# Upper.net
KiCad netlist of a schematic drawn in Altium Designer
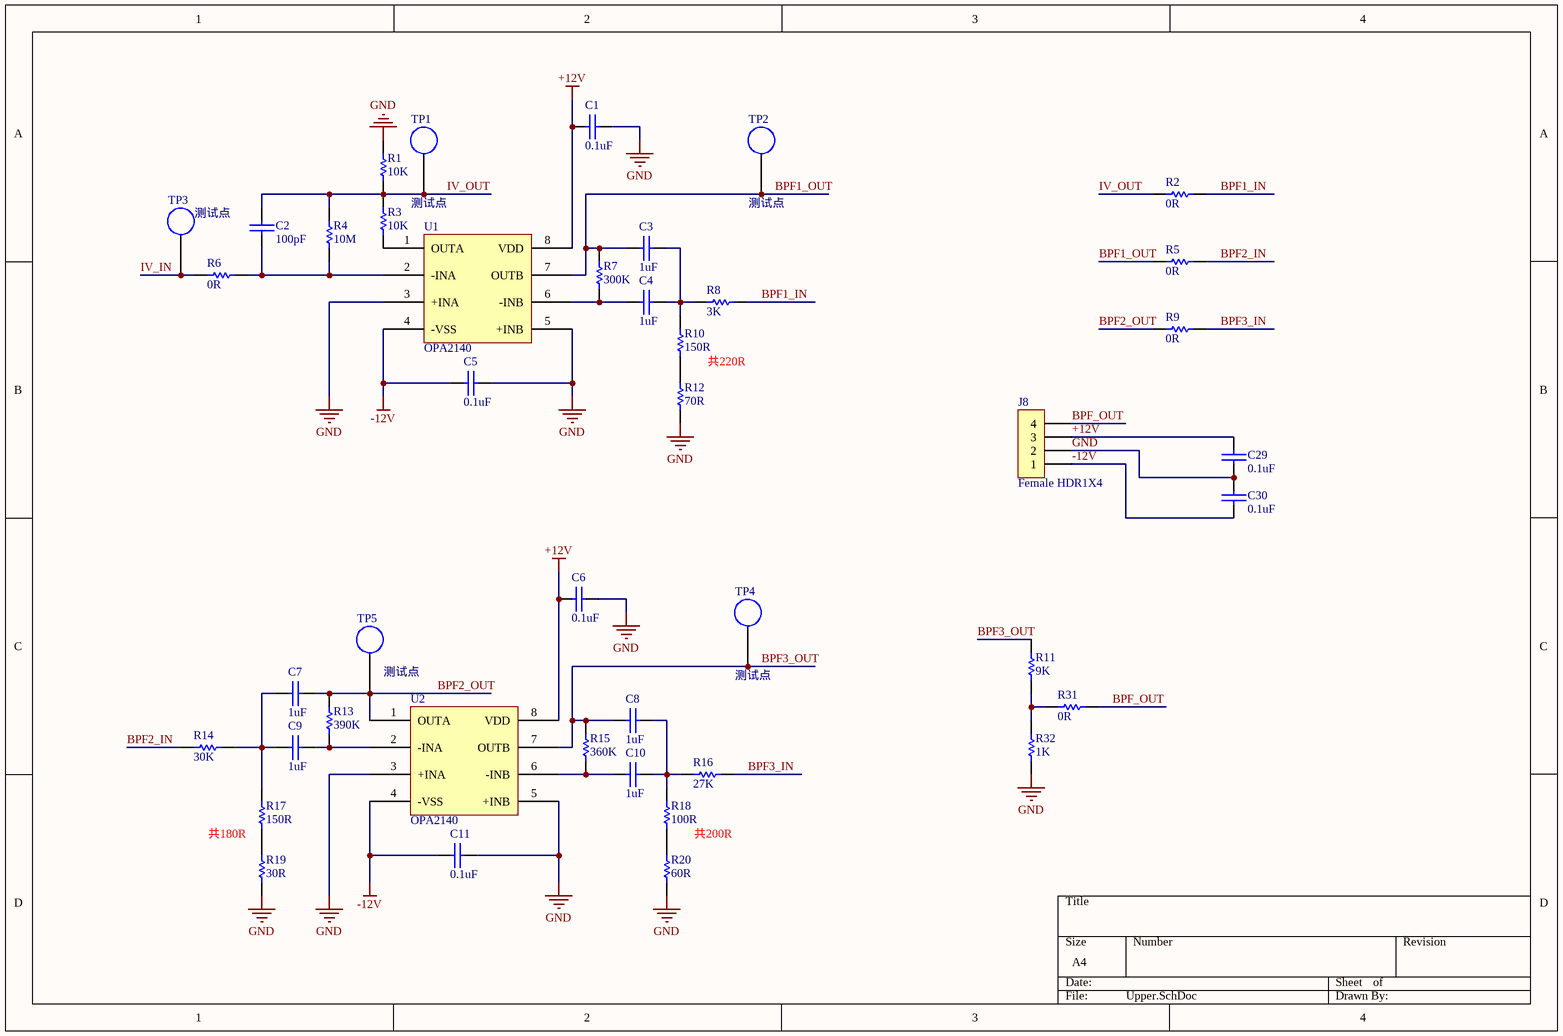
[diagram p0: Upper.SchDoc]

(export (version "E")
  (design (tool "Eeschema 10.0.6"))
  (components
    (comp (ref "C1")
      (value "0.1uF")
      (footprint "0603C")
      (description "无极性电容")
      (libsource (lib "电容") (part "CAP"))
    )
    (comp (ref "C2")
      (value "100pF")
      (footprint "0603C")
      (description "无极性电容")
      (libsource (lib "电容") (part "CAP"))
    )
    (comp (ref "C3")
      (value "1uF")
      (footprint "0603C")
      (description "无极性电容")
      (libsource (lib "电容") (part "CAP"))
    )
    (comp (ref "C4")
      (value "1uF")
      (footprint "0603C")
      (description "无极性电容")
      (libsource (lib "电容") (part "CAP"))
    )
    (comp (ref "C5")
      (value "0.1uF")
      (footprint "0603C")
      (description "无极性电容")
      (libsource (lib "电容") (part "CAP"))
    )
    (comp (ref "C6")
      (value "0.1uF")
      (footprint "0603C")
      (description "无极性电容")
      (libsource (lib "电容") (part "CAP"))
    )
    (comp (ref "C7")
      (value "1uF")
      (footprint "1206C")
      (description "无极性电容")
      (libsource (lib "电容") (part "CAP"))
    )
    (comp (ref "C8")
      (value "1uF")
      (footprint "0603C")
      (description "无极性电容")
      (libsource (lib "电容") (part "CAP"))
    )
    (comp (ref "C9")
      (value "1uF")
      (footprint "1206C")
      (description "无极性电容")
      (libsource (lib "电容") (part "CAP"))
    )
    (comp (ref "C10")
      (value "1uF")
      (footprint "0603C")
      (description "无极性电容")
      (libsource (lib "电容") (part "CAP"))
    )
    (comp (ref "C11")
      (value "0.1uF")
      (footprint "0603C")
      (description "无极性电容")
      (libsource (lib "电容") (part "CAP"))
    )
    (comp (ref "C29")
      (value "0.1uF")
      (footprint "0603C")
      (description "无极性电容")
      (libsource (lib "电容") (part "CAP"))
    )
    (comp (ref "C30")
      (value "0.1uF")
      (footprint "0603C")
      (description "无极性电容")
      (libsource (lib "电容") (part "CAP"))
    )
    (comp (ref "J8")
      (value "Female HDR1X4")
      (footprint "Fe-HDR1X4/2.54-S")
      (libsource (lib "排母") (part "Female HDR1X4"))
    )
    (comp (ref "R1") (value "10K") (footprint "0603R") (libsource (lib "电阻") (part "RES")))
    (comp (ref "R2") (value "0R") (footprint "0603R") (libsource (lib "电阻") (part "RES")))
    (comp (ref "R3") (value "10K") (footprint "0603R") (libsource (lib "电阻") (part "RES")))
    (comp (ref "R4") (value "10M") (footprint "0603R") (libsource (lib "电阻") (part "RES")))
    (comp (ref "R5") (value "0R") (footprint "0603R") (libsource (lib "电阻") (part "RES")))
    (comp (ref "R6") (value "0R") (footprint "0603R") (libsource (lib "电阻") (part "RES")))
    (comp (ref "R7") (value "300K") (footprint "0603R") (libsource (lib "电阻") (part "RES")))
    (comp (ref "R8") (value "3K") (footprint "0603R") (libsource (lib "电阻") (part "RES")))
    (comp (ref "R9") (value "0R") (footprint "0603R") (libsource (lib "电阻") (part "RES")))
    (comp (ref "R10") (value "150R") (footprint "0603R") (libsource (lib "电阻") (part "RES")))
    (comp (ref "R11") (value "9K") (footprint "0603R") (libsource (lib "电阻") (part "RES")))
    (comp (ref "R12") (value "70R") (footprint "0603R") (libsource (lib "电阻") (part "RES")))
    (comp (ref "R13") (value "390K") (footprint "0603R") (libsource (lib "电阻") (part "RES")))
    (comp (ref "R14") (value "30K") (footprint "0603R") (libsource (lib "电阻") (part "RES")))
    (comp (ref "R15") (value "360K") (footprint "0603R") (libsource (lib "电阻") (part "RES")))
    (comp (ref "R16") (value "27K") (footprint "0603R") (libsource (lib "电阻") (part "RES")))
    (comp (ref "R17") (value "150R") (footprint "0603R") (libsource (lib "电阻") (part "RES")))
    (comp (ref "R18") (value "100R") (footprint "0603R") (libsource (lib "电阻") (part "RES")))
    (comp (ref "R19") (value "30R") (footprint "0603R") (libsource (lib "电阻") (part "RES")))
    (comp (ref "R20") (value "60R") (footprint "0603R") (libsource (lib "电阻") (part "RES")))
    (comp (ref "R31") (value "0R") (footprint "0603R") (libsource (lib "电阻") (part "RES")))
    (comp (ref "R32") (value "1K") (footprint "0603R") (libsource (lib "电阻") (part "RES")))
    (comp (ref "TP1") (value "测试点") (footprint "TP") (libsource (lib "固定柱和测试点") (part "测试点")))
    (comp (ref "TP2") (value "测试点") (footprint "TP") (libsource (lib "固定柱和测试点") (part "测试点")))
    (comp (ref "TP3") (value "测试点") (footprint "TP") (libsource (lib "固定柱和测试点") (part "测试点")))
    (comp (ref "TP4") (value "测试点") (footprint "TP") (libsource (lib "固定柱和测试点") (part "测试点")))
    (comp (ref "TP5") (value "测试点") (footprint "TP") (libsource (lib "固定柱和测试点") (part "测试点")))
    (comp (ref "U1") (value "OPA2140") (footprint "SOP8") (libsource (lib "未分类IC") (part "NE5532")))
    (comp (ref "U2") (value "OPA2140") (footprint "SOP8") (libsource (lib "未分类IC") (part "NE5532")))
  )
  (nets
    (net (code "1") (name "+12V") (class "Default")
      (node (ref "C1") (pin "1") (pinfunction "1_1") (pintype "passive"))
      (node (ref "C29") (pin "2") (pinfunction "2_2") (pintype "passive"))
      (node (ref "C6") (pin "1") (pinfunction "1_1") (pintype "passive"))
      (node (ref "J8") (pin "3") (pinfunction "3_3") (pintype "passive"))
      (node (ref "U1") (pin "8") (pinfunction "VDD_8") (pintype "passive"))
      (node (ref "U2") (pin "8") (pinfunction "VDD_8") (pintype "passive"))
    )
    (net (code "2") (name "-12V") (class "Default")
      (node (ref "C11") (pin "1") (pinfunction "1_1") (pintype "passive"))
      (node (ref "C30") (pin "1") (pinfunction "1_1") (pintype "passive"))
      (node (ref "C5") (pin "1") (pinfunction "1_1") (pintype "passive"))
      (node (ref "J8") (pin "1") (pinfunction "1_1") (pintype "passive"))
      (node (ref "U1") (pin "4") (pinfunction "-VSS_4") (pintype "passive"))
      (node (ref "U2") (pin "4") (pinfunction "-VSS_4") (pintype "passive"))
    )
    (net (code "3") (name "/BPF1_IN") (class "Default")
      (node (ref "R2") (pin "2") (pinfunction "2_2") (pintype "passive"))
      (node (ref "R8") (pin "1") (pinfunction "1_1") (pintype "passive"))
    )
    (net (code "4") (name "/BPF1_OUT") (class "Default")
      (node (ref "C3") (pin "2") (pinfunction "2_2") (pintype "passive"))
      (node (ref "R5") (pin "1") (pinfunction "1_1") (pintype "passive"))
      (node (ref "R7") (pin "2") (pinfunction "2_2") (pintype "passive"))
      (node (ref "TP2") (pin "1") (pinfunction "TP_1") (pintype "passive"))
      (node (ref "U1") (pin "7") (pinfunction "OUTB_7") (pintype "passive"))
    )
    (net (code "5") (name "/BPF2_IN") (class "Default")
      (node (ref "R14") (pin "2") (pinfunction "2_2") (pintype "passive"))
      (node (ref "R5") (pin "2") (pinfunction "2_2") (pintype "passive"))
    )
    (net (code "6") (name "/BPF2_OUT") (class "Default")
      (node (ref "C7") (pin "1") (pinfunction "1_1") (pintype "passive"))
      (node (ref "R13") (pin "2") (pinfunction "2_2") (pintype "passive"))
      (node (ref "R9") (pin "1") (pinfunction "1_1") (pintype "passive"))
      (node (ref "TP5") (pin "1") (pinfunction "TP_1") (pintype "passive"))
      (node (ref "U2") (pin "1") (pinfunction "OUTA_1") (pintype "passive"))
    )
    (net (code "7") (name "/BPF3_IN") (class "Default")
      (node (ref "R16") (pin "1") (pinfunction "1_1") (pintype "passive"))
      (node (ref "R9") (pin "2") (pinfunction "2_2") (pintype "passive"))
    )
    (net (code "8") (name "/BPF3_OUT") (class "Default")
      (node (ref "C8") (pin "2") (pinfunction "2_2") (pintype "passive"))
      (node (ref "R11") (pin "2") (pinfunction "2_2") (pintype "passive"))
      (node (ref "R15") (pin "2") (pinfunction "2_2") (pintype "passive"))
      (node (ref "TP4") (pin "1") (pinfunction "TP_1") (pintype "passive"))
      (node (ref "U2") (pin "7") (pinfunction "OUTB_7") (pintype "passive"))
    )
    (net (code "9") (name "/BPF_OUT") (class "Default")
      (node (ref "J8") (pin "4") (pinfunction "4_4") (pintype "passive"))
      (node (ref "R31") (pin "1") (pinfunction "1_1") (pintype "passive"))
    )
    (net (code "10") (name "/IV_IN") (class "Default")
      (node (ref "R6") (pin "2") (pinfunction "2_2") (pintype "passive"))
      (node (ref "TP3") (pin "1") (pinfunction "TP_1") (pintype "passive"))
    )
    (net (code "11") (name "/IV_OUT") (class "Default")
      (node (ref "C2") (pin "1") (pinfunction "1_1") (pintype "passive"))
      (node (ref "R1") (pin "1") (pinfunction "1_1") (pintype "passive"))
      (node (ref "R2") (pin "1") (pinfunction "1_1") (pintype "passive"))
      (node (ref "R3") (pin "2") (pinfunction "2_2") (pintype "passive"))
      (node (ref "R4") (pin "2") (pinfunction "2_2") (pintype "passive"))
      (node (ref "TP1") (pin "1") (pinfunction "TP_1") (pintype "passive"))
    )
    (net (code "12") (name "GND") (class "Default")
      (node (ref "C1") (pin "2") (pinfunction "2_2") (pintype "passive"))
      (node (ref "C11") (pin "2") (pinfunction "2_2") (pintype "passive"))
      (node (ref "C29") (pin "1") (pinfunction "1_1") (pintype "passive"))
      (node (ref "C30") (pin "2") (pinfunction "2_2") (pintype "passive"))
      (node (ref "C5") (pin "2") (pinfunction "2_2") (pintype "passive"))
      (node (ref "C6") (pin "2") (pinfunction "2_2") (pintype "passive"))
      (node (ref "J8") (pin "2") (pinfunction "2_2") (pintype "passive"))
      (node (ref "R1") (pin "2") (pinfunction "2_2") (pintype "passive"))
      (node (ref "R12") (pin "2") (pinfunction "2_2") (pintype "passive"))
      (node (ref "R19") (pin "2") (pinfunction "2_2") (pintype "passive"))
      (node (ref "R20") (pin "2") (pinfunction "2_2") (pintype "passive"))
      (node (ref "R32") (pin "1") (pinfunction "1_1") (pintype "passive"))
      (node (ref "U1") (pin "3") (pinfunction "+INA_3") (pintype "passive"))
      (node (ref "U1") (pin "5") (pinfunction "+INB_5") (pintype "passive"))
      (node (ref "U2") (pin "3") (pinfunction "+INA_3") (pintype "passive"))
      (node (ref "U2") (pin "5") (pinfunction "+INB_5") (pintype "passive"))
    )
    (net (code "13") (name "Net-(C3-Pad1)") (class "Default")
      (node (ref "C3") (pin "1") (pinfunction "1_1") (pintype "passive"))
      (node (ref "C4") (pin "2") (pinfunction "2_2") (pintype "passive"))
      (node (ref "R10") (pin "1") (pinfunction "1_1") (pintype "passive"))
      (node (ref "R8") (pin "2") (pinfunction "2_2") (pintype "passive"))
    )
    (net (code "14") (name "Net-(C7-Pad2)") (class "Default")
      (node (ref "C7") (pin "2") (pinfunction "2_2") (pintype "passive"))
      (node (ref "C9") (pin "1") (pinfunction "1_1") (pintype "passive"))
      (node (ref "R14") (pin "1") (pinfunction "1_1") (pintype "passive"))
      (node (ref "R17") (pin "1") (pinfunction "1_1") (pintype "passive"))
    )
    (net (code "15") (name "Net-(C10-Pad2)") (class "Default")
      (node (ref "C10") (pin "2") (pinfunction "2_2") (pintype "passive"))
      (node (ref "C8") (pin "1") (pinfunction "1_1") (pintype "passive"))
      (node (ref "R16") (pin "2") (pinfunction "2_2") (pintype "passive"))
      (node (ref "R18") (pin "1") (pinfunction "1_1") (pintype "passive"))
    )
    (net (code "16") (name "Net-(R10-Pad2)") (class "Default")
      (node (ref "R10") (pin "2") (pinfunction "2_2") (pintype "passive"))
      (node (ref "R12") (pin "1") (pinfunction "1_1") (pintype "passive"))
    )
    (net (code "17") (name "Net-(R11-Pad1)") (class "Default")
      (node (ref "R11") (pin "1") (pinfunction "1_1") (pintype "passive"))
      (node (ref "R31") (pin "2") (pinfunction "2_2") (pintype "passive"))
      (node (ref "R32") (pin "2") (pinfunction "2_2") (pintype "passive"))
    )
    (net (code "18") (name "Net-(R17-Pad2)") (class "Default")
      (node (ref "R17") (pin "2") (pinfunction "2_2") (pintype "passive"))
      (node (ref "R19") (pin "1") (pinfunction "1_1") (pintype "passive"))
    )
    (net (code "19") (name "Net-(R18-Pad2)") (class "Default")
      (node (ref "R18") (pin "2") (pinfunction "2_2") (pintype "passive"))
      (node (ref "R20") (pin "1") (pinfunction "1_1") (pintype "passive"))
    )
    (net (code "20") (name "Net-(U1--INA)") (class "Default")
      (node (ref "C2") (pin "2") (pinfunction "2_2") (pintype "passive"))
      (node (ref "R4") (pin "1") (pinfunction "1_1") (pintype "passive"))
      (node (ref "R6") (pin "1") (pinfunction "1_1") (pintype "passive"))
      (node (ref "U1") (pin "2") (pinfunction "-INA_2") (pintype "passive"))
    )
    (net (code "21") (name "Net-(U1--INB)") (class "Default")
      (node (ref "C4") (pin "1") (pinfunction "1_1") (pintype "passive"))
      (node (ref "R7") (pin "1") (pinfunction "1_1") (pintype "passive"))
      (node (ref "U1") (pin "6") (pinfunction "-INB_6") (pintype "passive"))
    )
    (net (code "22") (name "Net-(U1-OUTA)") (class "Default")
      (node (ref "R3") (pin "1") (pinfunction "1_1") (pintype "passive"))
      (node (ref "U1") (pin "1") (pinfunction "OUTA_1") (pintype "passive"))
    )
    (net (code "23") (name "Net-(U2--INA)") (class "Default")
      (node (ref "C9") (pin "2") (pinfunction "2_2") (pintype "passive"))
      (node (ref "R13") (pin "1") (pinfunction "1_1") (pintype "passive"))
      (node (ref "U2") (pin "2") (pinfunction "-INA_2") (pintype "passive"))
    )
    (net (code "24") (name "Net-(U2--INB)") (class "Default")
      (node (ref "C10") (pin "1") (pinfunction "1_1") (pintype "passive"))
      (node (ref "R15") (pin "1") (pinfunction "1_1") (pintype "passive"))
      (node (ref "U2") (pin "6") (pinfunction "-INB_6") (pintype "passive"))
    )
  )
)
